# digital_socket.net
KiCad netlist of a schematic drawn in Altium Designer
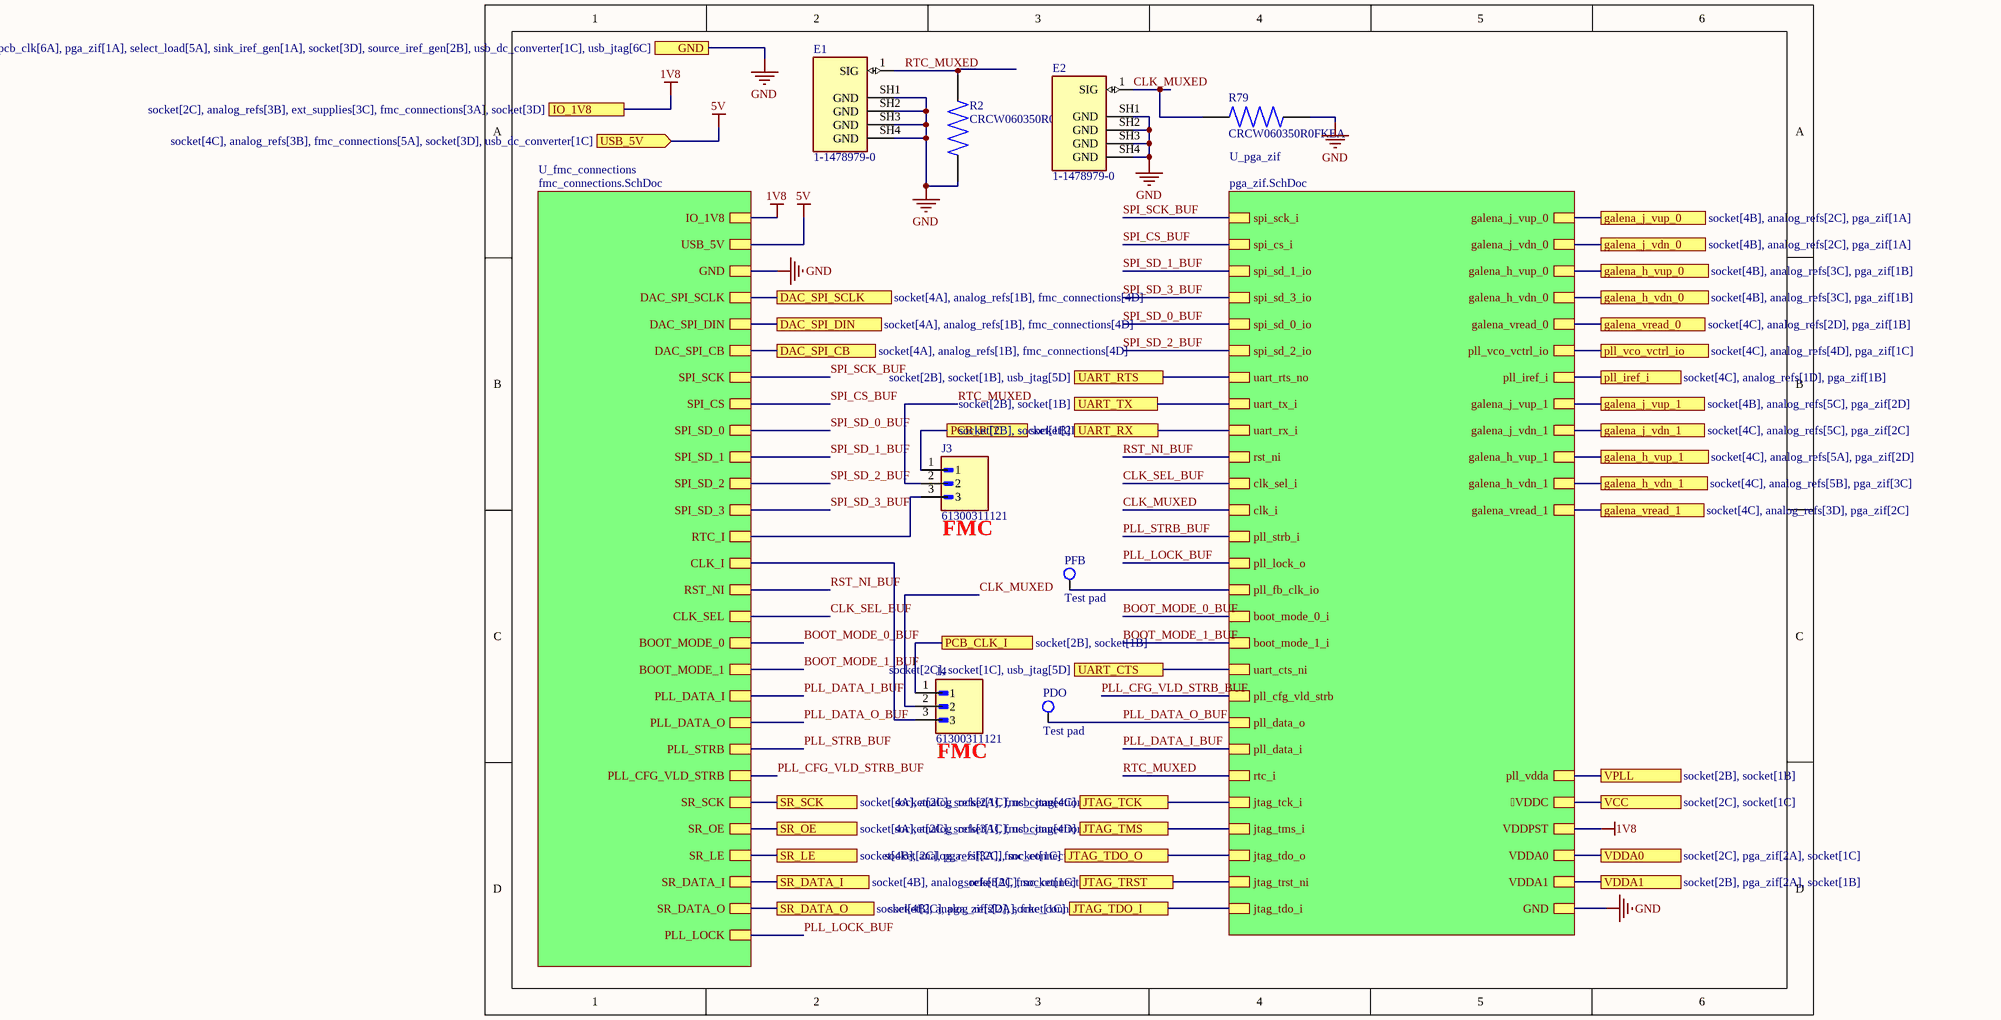
[diagram p0: digital_socket.SchDoc]

(export (version "E")
  (design (tool "Eeschema 10.0.6"))
  (components
    (comp (ref "E1")
      (value "1-1478979-0")
      (footprint "TE_1-1478979-0")
      (libsource (lib "1-1478979-0") (part "1-1478979-0"))
    )
    (comp (ref "E2")
      (value "1-1478979-0")
      (footprint "TE_1-1478979-0")
      (libsource (lib "1-1478979-0") (part "1-1478979-0"))
    )
    (comp (ref "J3")
      (value "61300311121")
      (footprint "WURTH_61300311121")
      (libsource (lib "61300311121") (part "61300311121"))
    )
    (comp (ref "J4")
      (value "61300311121")
      (footprint "WURTH_61300311121")
      (libsource (lib "61300311121") (part "61300311121"))
    )
    (comp (ref "PDO")
      (value "Test pad")
      (footprint "Test Pad")
      (libsource (lib "Connectors") (part "Test pad"))
    )
    (comp (ref "PFB")
      (value "Test pad")
      (footprint "Test Pad")
      (libsource (lib "Connectors") (part "Test pad"))
    )
    (comp (ref "R2")
      (value "CRCW060350R0FKEA")
      (footprint "RESC1508X50N")
      (fields (field (name "MF") "Vishay Intertechnology"))
      (libsource (lib "CRCW060350R0FKEA") (part "CRCW060350R0FKEA"))
    )
    (comp (ref "R79")
      (value "CRCW060350R0FKEA")
      (footprint "RESC1508X50N")
      (fields (field (name "MF") "Vishay Intertechnology"))
      (libsource (lib "CRCW060350R0FKEA") (part "CRCW060350R0FKEA"))
    )
  )
  (nets
    (net (code "3") (name "/CLK_I") (class "Default")
      (node (ref "J4") (pin "3") (pinfunction "3_3") (pintype "passive"))
    )
    (net (code "4") (name "/CLK_MUXED") (class "Default")
      (node (ref "E2") (pin "1") (pinfunction "SIG_1") (pintype "bidirectional"))
      (node (ref "J4") (pin "2") (pinfunction "2_2") (pintype "passive"))
      (node (ref "R79") (pin "1") (pinfunction "1_1") (pintype "passive"))
    )
    (net (code "14") (name "/PCB_CLK_I") (class "Default")
      (node (ref "J4") (pin "1") (pinfunction "1_1") (pintype "passive"))
    )
    (net (code "15") (name "/PCB_RTC") (class "Default")
      (node (ref "J3") (pin "1") (pinfunction "1_1") (pintype "passive"))
    )
    (net (code "18") (name "/PLL_DATA_O_BUF") (class "Default")
      (node (ref "PDO") (pin "1") (pintype "passive"))
    )
    (net (code "22") (name "/RTC_I") (class "Default")
      (node (ref "J3") (pin "3") (pinfunction "3_3") (pintype "passive"))
    )
    (net (code "23") (name "/RTC_MUXED") (class "Default")
      (node (ref "E1") (pin "1") (pinfunction "SIG_1") (pintype "bidirectional"))
      (node (ref "J3") (pin "2") (pinfunction "2_2") (pintype "passive"))
      (node (ref "R2") (pin "2") (pinfunction "2_2") (pintype "passive"))
    )
    (net (code "54") (name "/pll_fb_clk_io") (class "Default")
      (node (ref "PFB") (pin "1") (pintype "passive"))
    )
    (net (code "59") (name "GND") (class "Default")
      (node (ref "E1") (pin "SH1") (pinfunction "GND_SH1") (pintype "power_in"))
      (node (ref "E1") (pin "SH2") (pinfunction "GND_SH2") (pintype "power_in"))
      (node (ref "E1") (pin "SH3") (pinfunction "GND_SH3") (pintype "power_in"))
      (node (ref "E1") (pin "SH4") (pinfunction "GND_SH4") (pintype "power_in"))
      (node (ref "E2") (pin "SH1") (pinfunction "GND_SH1") (pintype "power_in"))
      (node (ref "E2") (pin "SH2") (pinfunction "GND_SH2") (pintype "power_in"))
      (node (ref "E2") (pin "SH3") (pinfunction "GND_SH3") (pintype "power_in"))
      (node (ref "E2") (pin "SH4") (pinfunction "GND_SH4") (pintype "power_in"))
      (node (ref "R2") (pin "1") (pinfunction "1_1") (pintype "passive"))
      (node (ref "R79") (pin "2") (pinfunction "2_2") (pintype "passive"))
    )
  )
)
